# attiny45-microcontrol-v3_0.net
KiCad netlist of a schematic drawn in EAGLE
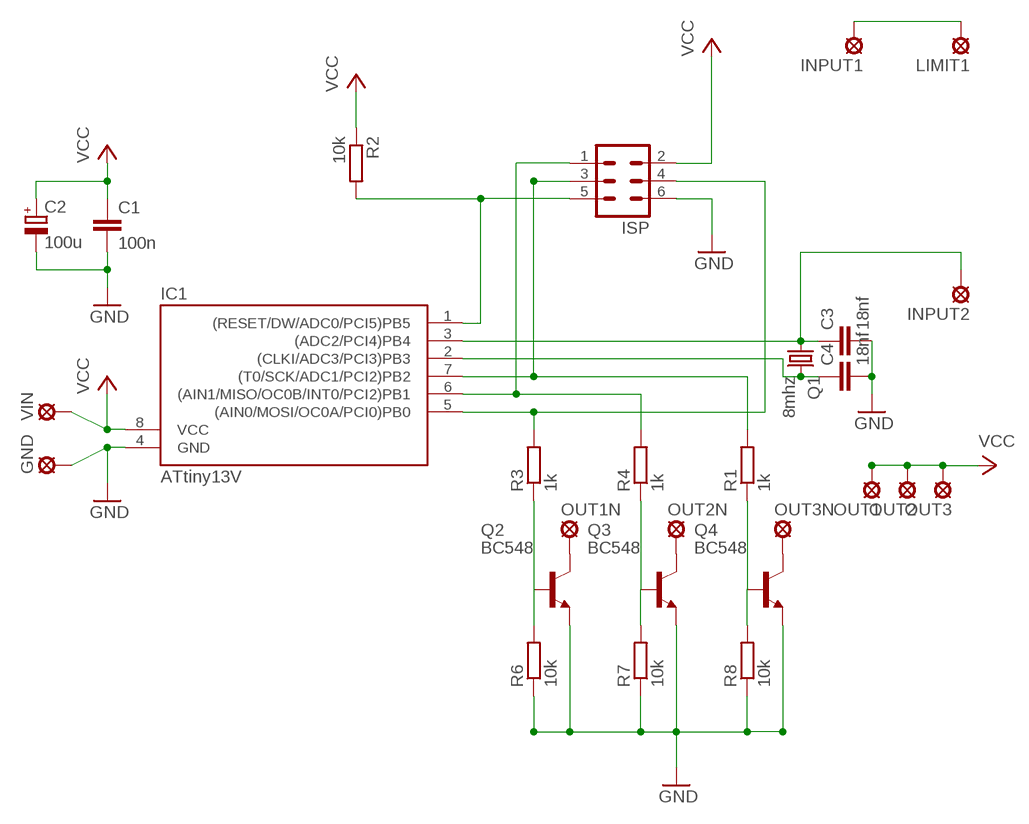
[diagram p0: schematic, sheet 1]

(export (version "E")
  (design (tool "Eeschema 10.0.6"))
  (components
    (comp (ref "C1")
      (value "100n")
      (footprint "eagle-import:C025-025X050")
      (libsource (lib "eagle-import") (part "C-EU025-025X050"))
    )
    (comp (ref "C2")
      (value "100u")
      (footprint "eagle-import:E2,5-6E")
      (libsource (lib "eagle-import") (part "CPOL-EUE2,5-6E"))
    )
    (comp (ref "C3")
      (value "18nf")
      (footprint "eagle-import:C5B2.5")
      (libsource (lib "eagle-import") (part "C5/2.5"))
    )
    (comp (ref "C4")
      (value "18nf")
      (footprint "eagle-import:C5B2.5")
      (libsource (lib "eagle-import") (part "C5/2.5"))
    )
    (comp (ref "GND")
      (value "LSP10")
      (footprint "eagle-import:LSP10")
      (libsource (lib "eagle-import") (part "LSP10"))
    )
    (comp (ref "IC1")
      (value "ATtiny13V")
      (footprint "eagle-import:DIL08")
      (libsource (lib "eagle-import") (part "ATTINY13P-20"))
    )
    (comp (ref "INPUT1")
      (value "LSP10")
      (footprint "eagle-import:LSP10")
      (libsource (lib "eagle-import") (part "LSP10"))
    )
    (comp (ref "INPUT2")
      (value "LSP10")
      (footprint "eagle-import:LSP10")
      (libsource (lib "eagle-import") (part "LSP10"))
    )
    (comp (ref "ISP")
      (value "MA03-2")
      (footprint "eagle-import:MA03-2")
      (libsource (lib "eagle-import") (part "MA03-2"))
    )
    (comp (ref "LIMIT1")
      (value "LSP10")
      (footprint "eagle-import:LSP10")
      (libsource (lib "eagle-import") (part "LSP10"))
    )
    (comp (ref "OUT1")
      (value "LSP10")
      (footprint "eagle-import:LSP10")
      (libsource (lib "eagle-import") (part "LSP10"))
    )
    (comp (ref "OUT1N")
      (value "LSP10")
      (footprint "eagle-import:LSP10")
      (libsource (lib "eagle-import") (part "LSP10"))
    )
    (comp (ref "OUT2")
      (value "LSP10")
      (footprint "eagle-import:LSP10")
      (libsource (lib "eagle-import") (part "LSP10"))
    )
    (comp (ref "OUT2N")
      (value "LSP10")
      (footprint "eagle-import:LSP10")
      (libsource (lib "eagle-import") (part "LSP10"))
    )
    (comp (ref "OUT3")
      (value "LSP10")
      (footprint "eagle-import:LSP10")
      (libsource (lib "eagle-import") (part "LSP10"))
    )
    (comp (ref "OUT3N")
      (value "LSP10")
      (footprint "eagle-import:LSP10")
      (libsource (lib "eagle-import") (part "LSP10"))
    )
    (comp (ref "Q1")
      (value "8mhz")
      (footprint "eagle-import:HC18U-V")
      (libsource (lib "eagle-import") (part "CRYSTALHC18U-V"))
    )
    (comp (ref "Q2")
      (value "BC548")
      (footprint "eagle-import:TO92-EBC")
      (libsource (lib "eagle-import") (part "BC548"))
    )
    (comp (ref "Q3")
      (value "BC548")
      (footprint "eagle-import:TO92-EBC")
      (libsource (lib "eagle-import") (part "BC548"))
    )
    (comp (ref "Q4")
      (value "BC548")
      (footprint "eagle-import:TO92-EBC")
      (libsource (lib "eagle-import") (part "BC548"))
    )
    (comp (ref "R1")
      (value "1k")
      (footprint "eagle-import:0204_7")
      (libsource (lib "eagle-import") (part "R-EU_0204/7"))
    )
    (comp (ref "R2")
      (value "10k")
      (footprint "eagle-import:0204V")
      (libsource (lib "eagle-import") (part "R-EU_0204/2V"))
    )
    (comp (ref "R3")
      (value "1k")
      (footprint "eagle-import:0204_7")
      (libsource (lib "eagle-import") (part "R-EU_0204/7"))
    )
    (comp (ref "R4")
      (value "1k")
      (footprint "eagle-import:0204_7")
      (libsource (lib "eagle-import") (part "R-EU_0204/7"))
    )
    (comp (ref "R6")
      (value "10k")
      (footprint "eagle-import:0204V")
      (libsource (lib "eagle-import") (part "R-EU_0204/2V"))
    )
    (comp (ref "R7")
      (value "10k")
      (footprint "eagle-import:0204V")
      (libsource (lib "eagle-import") (part "R-EU_0204/2V"))
    )
    (comp (ref "R8")
      (value "10k")
      (footprint "eagle-import:0204V")
      (libsource (lib "eagle-import") (part "R-EU_0204/2V"))
    )
    (comp (ref "VIN")
      (value "LSP10")
      (footprint "eagle-import:LSP10")
      (libsource (lib "eagle-import") (part "LSP10"))
    )
  )
  (nets
    (net (code "1") (name "GND") (class "Default")
      (node (ref "C1") (pin "2") (pinfunction "2_2") (pintype "passive"))
      (node (ref "C2") (pin "-") (pinfunction "-_-") (pintype "passive"))
      (node (ref "C3") (pin "2") (pinfunction "2_2") (pintype "passive"))
      (node (ref "C4") (pin "2") (pinfunction "2_2") (pintype "passive"))
      (node (ref "GND") (pin "MP") (pinfunction "MP_MP") (pintype "passive"))
      (node (ref "IC1") (pin "4") (pinfunction "GND_4") (pintype "power_in"))
      (node (ref "ISP") (pin "6") (pinfunction "6_6") (pintype "passive"))
      (node (ref "Q2") (pin "E") (pinfunction "E_E") (pintype "passive"))
      (node (ref "Q3") (pin "E") (pinfunction "E_E") (pintype "passive"))
      (node (ref "Q4") (pin "E") (pinfunction "E_E") (pintype "passive"))
      (node (ref "R6") (pin "1") (pinfunction "1_1") (pintype "passive"))
      (node (ref "R7") (pin "1") (pinfunction "1_1") (pintype "passive"))
      (node (ref "R8") (pin "1") (pinfunction "1_1") (pintype "passive"))
    )
    (net (code "2") (name "Net-(IC1-(ADC2{slash}PCI4)PB4)") (class "Default")
      (node (ref "C3") (pin "1") (pinfunction "1_1") (pintype "passive"))
      (node (ref "IC1") (pin "3") (pinfunction "(ADC2/PCI4)PB4_3") (pintype "bidirectional"))
      (node (ref "INPUT2") (pin "MP") (pinfunction "MP_MP") (pintype "passive"))
      (node (ref "Q1") (pin "1") (pinfunction "1_1") (pintype "passive"))
    )
    (net (code "3") (name "Net-(IC1-(AIN0{slash}MOSI{slash}OC0A{slash}PCI0)PB0)") (class "Default")
      (node (ref "IC1") (pin "5") (pinfunction "(AIN0/MOSI/OC0A/PCI0)PB0_5") (pintype "bidirectional"))
      (node (ref "ISP") (pin "4") (pinfunction "4_4") (pintype "passive"))
      (node (ref "R3") (pin "2") (pinfunction "2_2") (pintype "passive"))
    )
    (net (code "4") (name "Net-(IC1-(AIN1{slash}MISO{slash}OC0B{slash}INT0{slash}PCI2)PB1)") (class "Default")
      (node (ref "IC1") (pin "6") (pinfunction "(AIN1/MISO/OC0B/INT0/PCI2)PB1_6") (pintype "bidirectional"))
      (node (ref "ISP") (pin "1") (pinfunction "1_1") (pintype "passive"))
      (node (ref "R4") (pin "2") (pinfunction "2_2") (pintype "passive"))
    )
    (net (code "5") (name "Net-(IC1-(CLKI{slash}ADC3{slash}PCI3)PB3)") (class "Default")
      (node (ref "C4") (pin "1") (pinfunction "1_1") (pintype "passive"))
      (node (ref "IC1") (pin "2") (pinfunction "(CLKI/ADC3/PCI3)PB3_2") (pintype "bidirectional"))
      (node (ref "Q1") (pin "2") (pinfunction "2_2") (pintype "passive"))
    )
    (net (code "6") (name "Net-(IC1-(RESET{slash}DW{slash}ADC0{slash}PCI5)PB5)") (class "Default")
      (node (ref "IC1") (pin "1") (pinfunction "(RESET/DW/ADC0/PCI5)PB5_1") (pintype "bidirectional"))
      (node (ref "ISP") (pin "5") (pinfunction "5_5") (pintype "passive"))
      (node (ref "R2") (pin "2") (pinfunction "2_2") (pintype "passive"))
    )
    (net (code "7") (name "Net-(IC1-(T0{slash}SCK{slash}ADC1{slash}PCI2)PB2)") (class "Default")
      (node (ref "IC1") (pin "7") (pinfunction "(T0/SCK/ADC1/PCI2)PB2_7") (pintype "bidirectional"))
      (node (ref "ISP") (pin "3") (pinfunction "3_3") (pintype "passive"))
      (node (ref "R1") (pin "2") (pinfunction "2_2") (pintype "passive"))
    )
    (net (code "8") (name "Net-(INPUT1-PadMP)") (class "Default")
      (node (ref "INPUT1") (pin "MP") (pinfunction "MP_MP") (pintype "passive"))
      (node (ref "LIMIT1") (pin "MP") (pinfunction "MP_MP") (pintype "passive"))
    )
    (net (code "9") (name "Net-(OUT1N-PadMP)") (class "Default")
      (node (ref "OUT1N") (pin "MP") (pinfunction "MP_MP") (pintype "passive"))
      (node (ref "Q2") (pin "C") (pinfunction "C_C") (pintype "passive"))
    )
    (net (code "10") (name "Net-(OUT2N-PadMP)") (class "Default")
      (node (ref "OUT2N") (pin "MP") (pinfunction "MP_MP") (pintype "passive"))
      (node (ref "Q3") (pin "C") (pinfunction "C_C") (pintype "passive"))
    )
    (net (code "11") (name "Net-(OUT3N-PadMP)") (class "Default")
      (node (ref "OUT3N") (pin "MP") (pinfunction "MP_MP") (pintype "passive"))
      (node (ref "Q4") (pin "C") (pinfunction "C_C") (pintype "passive"))
    )
    (net (code "12") (name "Net-(Q2-PadB)") (class "Default")
      (node (ref "Q2") (pin "B") (pinfunction "B_B") (pintype "passive"))
      (node (ref "R3") (pin "1") (pinfunction "1_1") (pintype "passive"))
      (node (ref "R6") (pin "2") (pinfunction "2_2") (pintype "passive"))
    )
    (net (code "13") (name "Net-(Q3-PadB)") (class "Default")
      (node (ref "Q3") (pin "B") (pinfunction "B_B") (pintype "passive"))
      (node (ref "R4") (pin "1") (pinfunction "1_1") (pintype "passive"))
      (node (ref "R7") (pin "2") (pinfunction "2_2") (pintype "passive"))
    )
    (net (code "14") (name "Net-(Q4-PadB)") (class "Default")
      (node (ref "Q4") (pin "B") (pinfunction "B_B") (pintype "passive"))
      (node (ref "R1") (pin "1") (pinfunction "1_1") (pintype "passive"))
      (node (ref "R8") (pin "2") (pinfunction "2_2") (pintype "passive"))
    )
    (net (code "15") (name "VCC") (class "Default")
      (node (ref "C1") (pin "1") (pinfunction "1_1") (pintype "passive"))
      (node (ref "C2") (pin "+") (pinfunction "+_+") (pintype "passive"))
      (node (ref "IC1") (pin "8") (pinfunction "VCC_8") (pintype "power_in"))
      (node (ref "ISP") (pin "2") (pinfunction "2_2") (pintype "passive"))
      (node (ref "OUT1") (pin "MP") (pinfunction "MP_MP") (pintype "passive"))
      (node (ref "OUT2") (pin "MP") (pinfunction "MP_MP") (pintype "passive"))
      (node (ref "OUT3") (pin "MP") (pinfunction "MP_MP") (pintype "passive"))
      (node (ref "R2") (pin "1") (pinfunction "1_1") (pintype "passive"))
      (node (ref "VIN") (pin "MP") (pinfunction "MP_MP") (pintype "passive"))
    )
  )
)
